# SaxStat_01.net
KiCad netlist of a schematic drawn in EasyEDA Pro
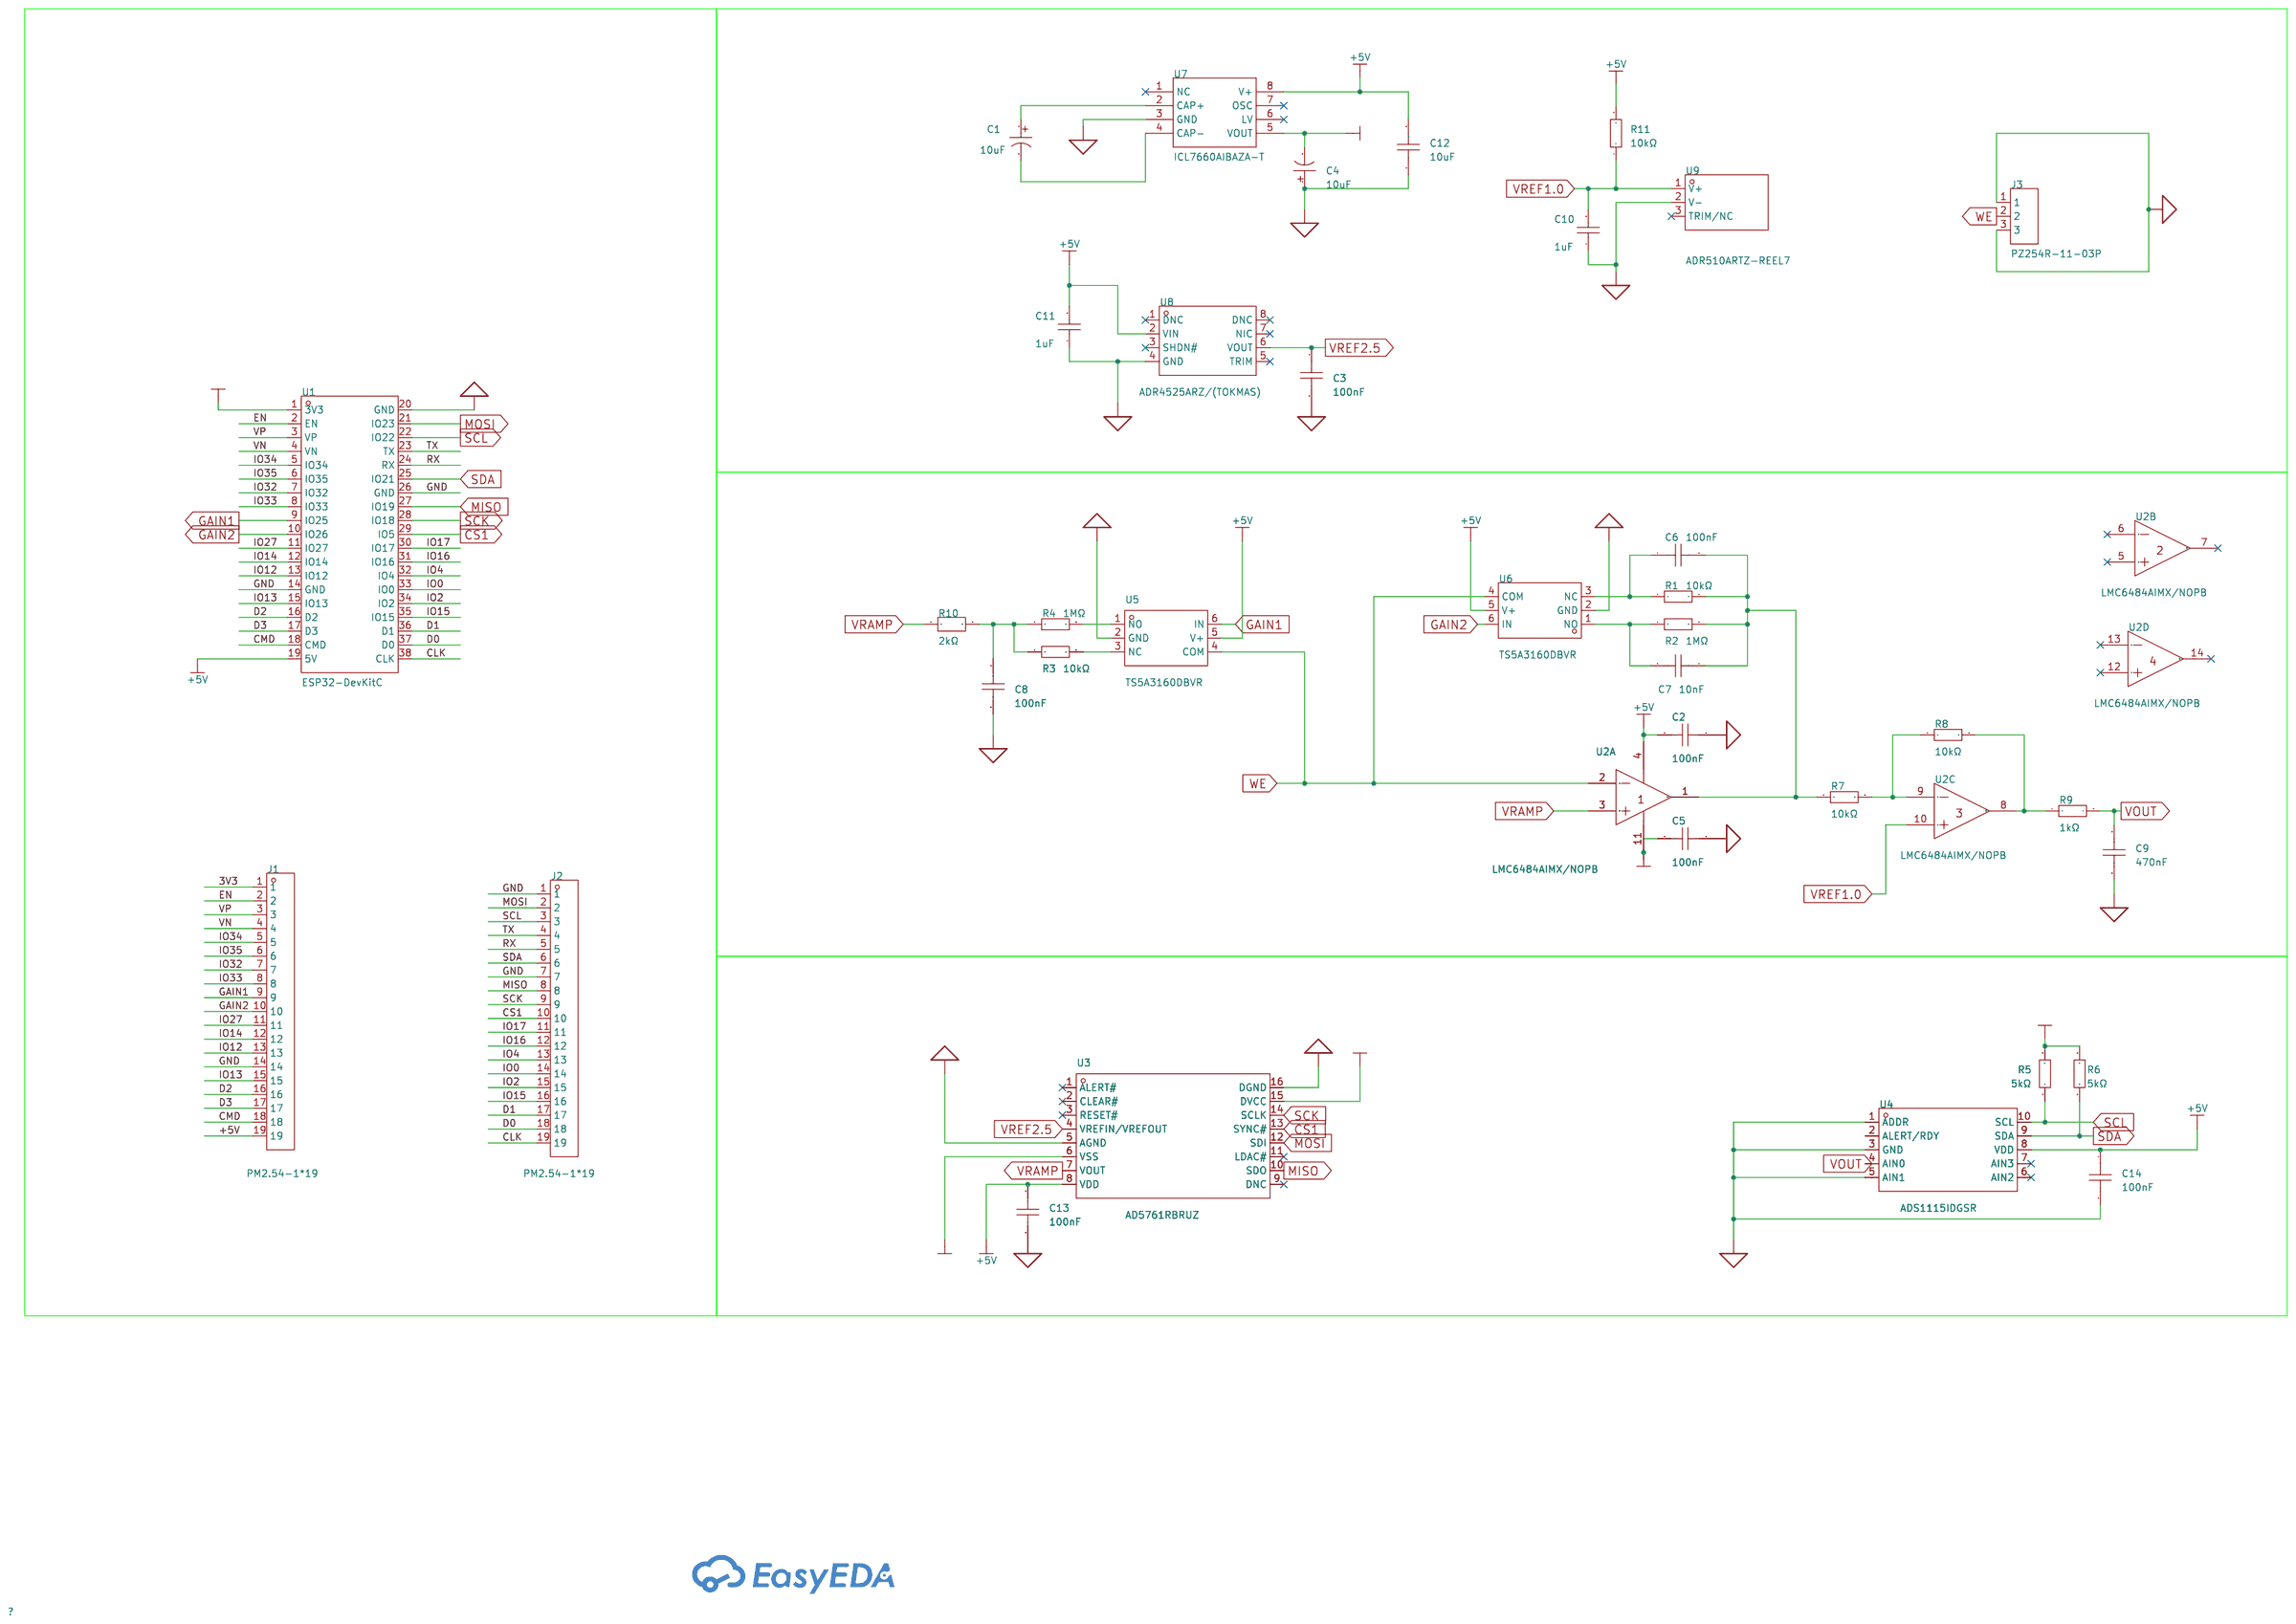
[diagram p0: schematic sheet]

(export (version "E")
  (design (tool "Eeschema 10.0.6"))
  (components
    (comp (ref "C1")
      (value "10uF")
      (footprint "easyedapro:CAP-SMD_BD4.0-L4.3-W4.3-FD")
      (fields (field (name "Manufacturer Part") "RVT1E100M0405") (field (name "Manufacturer") "HONOR(荣誉)"))
      (libsource (lib "easyedapro") (part "RVT1E100M0405"))
    )
    (comp (ref "C2")
      (value "100nF")
      (footprint "easyedapro:C0201")
      (fields
        (field (name "Manufacturer Part") "CL03A104KQ3NNNC")
        (field (name "Manufacturer") "SAMSUNG(三星)")
      )
      (libsource (lib "easyedapro") (part "CL03A104KQ3NNNC"))
    )
    (comp (ref "C3")
      (value "100nF")
      (footprint "easyedapro:C0201")
      (fields
        (field (name "Manufacturer Part") "CL03A104KQ3NNNC")
        (field (name "Manufacturer") "SAMSUNG(三星)")
      )
      (libsource (lib "easyedapro") (part "CL03A104KQ3NNNC"))
    )
    (comp (ref "C4")
      (value "10uF")
      (footprint "easyedapro:CAP-SMD_BD4.0-L4.3-W4.3-FD")
      (fields (field (name "Manufacturer Part") "RVT1E100M0405") (field (name "Manufacturer") "HONOR(荣誉)"))
      (libsource (lib "easyedapro") (part "RVT1E100M0405"))
    )
    (comp (ref "C5")
      (value "100nF")
      (footprint "easyedapro:C0201")
      (fields
        (field (name "Manufacturer Part") "CL03A104KQ3NNNC")
        (field (name "Manufacturer") "SAMSUNG(三星)")
      )
      (libsource (lib "easyedapro") (part "CL03A104KQ3NNNC"))
    )
    (comp (ref "C6")
      (value "100nF")
      (footprint "easyedapro:C0201")
      (fields
        (field (name "Manufacturer Part") "CL03A104KQ3NNNC")
        (field (name "Manufacturer") "SAMSUNG(三星)")
      )
      (libsource (lib "easyedapro") (part "CL03A104KQ3NNNC"))
    )
    (comp (ref "C7")
      (value "10nF")
      (footprint "easyedapro:C0201")
      (fields
        (field (name "Manufacturer Part") "CL03A103KP3NNNC")
        (field (name "Manufacturer") "SAMSUNG(三星)")
      )
      (libsource (lib "easyedapro") (part "CL03A103KP3NNNC"))
    )
    (comp (ref "C8")
      (value "100nF")
      (footprint "easyedapro:C0201")
      (fields
        (field (name "Manufacturer Part") "CL03A104KQ3NNNC")
        (field (name "Manufacturer") "SAMSUNG(三星)")
      )
      (libsource (lib "easyedapro") (part "CL03A104KQ3NNNC"))
    )
    (comp (ref "C9")
      (value "470nF")
      (footprint "easyedapro:C0201")
      (fields
        (field (name "Manufacturer Part") "CL03A474KQ3NNNC")
        (field (name "Manufacturer") "SAMSUNG(三星)")
      )
      (libsource (lib "easyedapro") (part "CL03A474KQ3NNNC"))
    )
    (comp (ref "C10")
      (value "1uF")
      (footprint "easyedapro:C0201")
      (fields
        (field (name "Manufacturer Part") "CL03A105MQ3CSNH")
        (field (name "Manufacturer") "SAMSUNG(三星)")
      )
      (libsource (lib "easyedapro") (part "CL03A105MQ3CSNH"))
    )
    (comp (ref "C11")
      (value "1uF")
      (footprint "easyedapro:C0201")
      (fields
        (field (name "Manufacturer Part") "CL03A105MQ3CSNH")
        (field (name "Manufacturer") "SAMSUNG(三星)")
      )
      (libsource (lib "easyedapro") (part "CL03A105MQ3CSNH"))
    )
    (comp (ref "C12")
      (value "10uF")
      (footprint "easyedapro:C0402")
      (fields
        (field (name "Manufacturer Part") "CL05A106MP5NUNC")
        (field (name "Manufacturer") "SAMSUNG(三星)")
      )
      (libsource (lib "easyedapro") (part "CL05A106MP5NUNC_C315248"))
    )
    (comp (ref "C13")
      (value "100nF")
      (footprint "easyedapro:C0201")
      (fields
        (field (name "Manufacturer Part") "CL03A104KQ3NNNC")
        (field (name "Manufacturer") "SAMSUNG(三星)")
      )
      (libsource (lib "easyedapro") (part "CL03A104KQ3NNNC"))
    )
    (comp (ref "C14")
      (value "100nF")
      (footprint "easyedapro:C0201")
      (fields
        (field (name "Manufacturer Part") "CL03A104KQ3NNNC")
        (field (name "Manufacturer") "SAMSUNG(三星)")
      )
      (libsource (lib "easyedapro") (part "CL03A104KQ3NNNC"))
    )
    (comp (ref "J1")
      (value "PM2.54-1*19")
      (footprint "easyedapro:HDR-TH_19P-P2.54-V-F")
      (description "Holes Structure:1x19P Pitch:2.54mm Number of Rows:Single Row Contact Plating:Gold")
      (fields (field (name "Manufacturer") "ZHOURI(洲日)"))
      (libsource (lib "easyedapro") (part "PM2.54-1*19"))
    )
    (comp (ref "J2")
      (value "PM2.54-1*19")
      (footprint "easyedapro:HDR-TH_19P-P2.54-V-F")
      (description "Holes Structure:1x19P Pitch:2.54mm Number of Rows:Single Row Contact Plating:Gold")
      (fields (field (name "Manufacturer") "ZHOURI(洲日)"))
      (libsource (lib "easyedapro") (part "PM2.54-1*19"))
    )
    (comp (ref "J3")
      (value "PZ254R-11-03P")
      (footprint "easyedapro:HDR-TH_3P-P2.54-H-M-W10.4")
      (fields (field (name "Manufacturer") "XFCN(兴飞)"))
      (libsource (lib "easyedapro") (part "PZ254R-11-03P"))
    )
    (comp (ref "R1")
      (value "10kΩ")
      (footprint "easyedapro:R0603")
      (fields (field (name "Manufacturer Part") "ARG03BTC1002") (field (name "Manufacturer") "Viking(光颉)"))
      (libsource (lib "easyedapro") (part "ARG03BTC1002"))
    )
    (comp (ref "R2")
      (value "1MΩ")
      (footprint "easyedapro:R0603")
      (fields (field (name "Manufacturer Part") "RT0603BRD071ML") (field (name "Manufacturer") "YAGEO(国巨)"))
      (libsource (lib "easyedapro") (part "RT0603BRD071ML"))
    )
    (comp (ref "R3")
      (value "10kΩ")
      (footprint "easyedapro:R0603")
      (fields (field (name "Manufacturer Part") "ARG03BTC1002") (field (name "Manufacturer") "Viking(光颉)"))
      (libsource (lib "easyedapro") (part "ARG03BTC1002"))
    )
    (comp (ref "R4")
      (value "1MΩ")
      (footprint "easyedapro:R0603")
      (fields (field (name "Manufacturer Part") "RT0603BRD071ML") (field (name "Manufacturer") "YAGEO(国巨)"))
      (libsource (lib "easyedapro") (part "RT0603BRD071ML"))
    )
    (comp (ref "R5")
      (value "5kΩ")
      (footprint "easyedapro:R0603")
      (fields (field (name "Manufacturer Part") "RT0603BRE075KL") (field (name "Manufacturer") "YAGEO(国巨)"))
      (libsource (lib "easyedapro") (part "RT0603BRE075KL"))
    )
    (comp (ref "R6")
      (value "5kΩ")
      (footprint "easyedapro:R0603")
      (fields (field (name "Manufacturer Part") "RT0603BRE075KL") (field (name "Manufacturer") "YAGEO(国巨)"))
      (libsource (lib "easyedapro") (part "RT0603BRE075KL"))
    )
    (comp (ref "R7")
      (value "10kΩ")
      (footprint "easyedapro:R0603")
      (fields (field (name "Manufacturer Part") "ARG03BTC1002") (field (name "Manufacturer") "Viking(光颉)"))
      (libsource (lib "easyedapro") (part "ARG03BTC1002"))
    )
    (comp (ref "R8")
      (value "10kΩ")
      (footprint "easyedapro:R0603")
      (fields (field (name "Manufacturer Part") "ARG03BTC1002") (field (name "Manufacturer") "Viking(光颉)"))
      (libsource (lib "easyedapro") (part "ARG03BTC1002"))
    )
    (comp (ref "R9")
      (value "1kΩ")
      (footprint "easyedapro:R0603")
      (fields (field (name "Manufacturer Part") "RT0603BRD071KL") (field (name "Manufacturer") "YAGEO(国巨)"))
      (libsource (lib "easyedapro") (part "RT0603BRD071KL"))
    )
    (comp (ref "R10")
      (value "2kΩ")
      (footprint "easyedapro:R0603")
      (fields (field (name "Manufacturer Part") "RT0603BRD072KL") (field (name "Manufacturer") "YAGEO(国巨)"))
      (libsource (lib "easyedapro") (part "RT0603BRD072KL"))
    )
    (comp (ref "R11")
      (value "10kΩ")
      (footprint "easyedapro:R0603")
      (fields (field (name "Manufacturer Part") "ARG03BTC1002") (field (name "Manufacturer") "Viking(光颉)"))
      (libsource (lib "easyedapro") (part "ARG03BTC1002"))
    )
    (comp (ref "U1")
      (value "ESP32-DevKitC")
      (footprint "easyedapro:BULETM-SMD_ESP32-DEVKITC")
      (fields (field (name "Manufacturer") "ESPRESSIF(乐鑫)"))
      (libsource (lib "easyedapro") (part "ESP32-DEVKITC"))
    )
    (comp (ref "U2")
      (value "LMC6484AIMX/NOPB")
      (footprint "easyedapro:SOIC-14_L8.7-W3.9-P1.27-LS6.0-BL")
      (fields (field (name "Manufacturer") "TI(德州仪器)"))
      (libsource (lib "easyedapro") (part "LMC6484AIMX/NOPB"))
    )
    (comp (ref "U3")
      (value "AD5761RBRUZ")
      (footprint "easyedapro:TSSOP-16_L5.0-W4.4-P0.65-LS6.4-TL")
      (fields (field (name "Manufacturer") "ADI(亚德诺)"))
      (libsource (lib "easyedapro") (part "AD5761RBRUZ"))
    )
    (comp (ref "U4")
      (value "ADS1115IDGSR")
      (footprint "easyedapro:MSOP-10_L3.0-W3.0-P0.50-LS5.0-BL")
      (fields (field (name "Manufacturer") "TI(德州仪器)"))
      (libsource (lib "easyedapro") (part "ADS1115IDGSR"))
    )
    (comp (ref "U5")
      (value "TS5A3160DBVR")
      (footprint "easyedapro:SOT-23-6_L2.9-W1.6-P0.95-LS2.8-BR")
      (fields (field (name "Manufacturer") "TI(德州仪器)"))
      (libsource (lib "easyedapro") (part "TS5A3160DBVR"))
    )
    (comp (ref "U6")
      (value "TS5A3160DBVR")
      (footprint "easyedapro:SOT-23-6_L2.9-W1.6-P0.95-LS2.8-BR")
      (fields (field (name "Manufacturer") "TI(德州仪器)"))
      (libsource (lib "easyedapro") (part "TS5A3160DBVR"))
    )
    (comp (ref "U7")
      (value "ICL7660AIBAZA-T")
      (footprint "easyedapro:SOIC-8_L5.0-W4.0-P1.27-LS6.0-BL")
      (fields (field (name "Manufacturer") "RENESAS(瑞萨)/IDT"))
      (libsource (lib "easyedapro") (part "ICL7660AIBAZA-T"))
    )
    (comp (ref "U8")
      (value "ADR4525ARZ/(TOKMAS)")
      (footprint "easyedapro:SOP-8_L4.9-W3.9-P1.27-LS6.0-BL")
      (fields (field (name "Manufacturer") "Tokmas(托克马斯)"))
      (libsource (lib "easyedapro") (part "ADR4525ARZ/(TOKMAS)"))
    )
    (comp (ref "U9")
      (value "ADR510ARTZ-REEL7")
      (footprint "easyedapro:SOT-23-3_L2.9-W1.3-P1.90-LS2.4-BR")
      (fields (field (name "Manufacturer") "ADI(亚德诺)"))
      (libsource (lib "easyedapro") (part "ADR510ARTZ-REEL7"))
    )
  )
  (nets
    (net (code "1") (name "+5V") (class "Default")
      (node (ref "C11") (pin "2") (pinfunction "2_2") (pintype "input"))
      (node (ref "C12") (pin "2") (pinfunction "2_2") (pintype "unspecified"))
      (node (ref "C13") (pin "1") (pinfunction "1_1") (pintype "unspecified"))
      (node (ref "C14") (pin "1") (pinfunction "1_1") (pintype "unspecified"))
      (node (ref "C2") (pin "1") (pinfunction "1_1") (pintype "unspecified"))
      (node (ref "J1") (pin "19") (pinfunction "19_19") (pintype "unspecified"))
      (node (ref "R11") (pin "2") (pinfunction "2_2") (pintype "unspecified"))
      (node (ref "U1") (pin "19") (pinfunction "5V_19") (pintype "unspecified"))
      (node (ref "U2") (pin "4") (pinfunction "V+_4") (pintype "unspecified"))
      (node (ref "U3") (pin "8") (pinfunction "VDD_8") (pintype "unspecified"))
      (node (ref "U4") (pin "8") (pinfunction "VDD_8") (pintype "unspecified"))
      (node (ref "U5") (pin "5") (pinfunction "V+_5") (pintype "unspecified"))
      (node (ref "U6") (pin "5") (pinfunction "V+_5") (pintype "unspecified"))
      (node (ref "U7") (pin "8") (pinfunction "V+_8") (pintype "unspecified"))
      (node (ref "U8") (pin "2") (pinfunction "VIN_2") (pintype "unspecified"))
    )
    (net (code "2") (name "-5V") (class "Default")
      (node (ref "C4") (pin "2") (pinfunction "2_2") (pintype "input"))
      (node (ref "C5") (pin "1") (pinfunction "1_1") (pintype "unspecified"))
      (node (ref "U2") (pin "11") (pinfunction "V-_11") (pintype "unspecified"))
      (node (ref "U3") (pin "6") (pinfunction "VSS_6") (pintype "unspecified"))
      (node (ref "U7") (pin "5") (pinfunction "VOUT_5") (pintype "unspecified"))
    )
    (net (code "3") (name "/CLK") (class "Default")
      (node (ref "J2") (pin "19") (pinfunction "19_19") (pintype "unspecified"))
      (node (ref "U1") (pin "38") (pinfunction "CLK_38") (pintype "unspecified"))
    )
    (net (code "4") (name "/CMD") (class "Default")
      (node (ref "J1") (pin "18") (pinfunction "18_18") (pintype "unspecified"))
      (node (ref "U1") (pin "18") (pinfunction "CMD_18") (pintype "unspecified"))
    )
    (net (code "5") (name "/D0") (class "Default")
      (node (ref "J2") (pin "18") (pinfunction "18_18") (pintype "unspecified"))
      (node (ref "U1") (pin "37") (pinfunction "D0_37") (pintype "unspecified"))
    )
    (net (code "6") (name "/D1") (class "Default")
      (node (ref "J2") (pin "17") (pinfunction "17_17") (pintype "unspecified"))
      (node (ref "U1") (pin "36") (pinfunction "D1_36") (pintype "unspecified"))
    )
    (net (code "7") (name "/D2") (class "Default")
      (node (ref "J1") (pin "16") (pinfunction "16_16") (pintype "unspecified"))
      (node (ref "U1") (pin "16") (pinfunction "D2_16") (pintype "unspecified"))
    )
    (net (code "8") (name "/D3") (class "Default")
      (node (ref "J1") (pin "17") (pinfunction "17_17") (pintype "unspecified"))
      (node (ref "U1") (pin "17") (pinfunction "D3_17") (pintype "unspecified"))
    )
    (net (code "9") (name "/EN") (class "Default")
      (node (ref "J1") (pin "2") (pinfunction "2_2") (pintype "unspecified"))
      (node (ref "U1") (pin "2") (pinfunction "EN_2") (pintype "unspecified"))
    )
    (net (code "10") (name "/IO0") (class "Default")
      (node (ref "J2") (pin "14") (pinfunction "14_14") (pintype "unspecified"))
      (node (ref "U1") (pin "33") (pinfunction "IO0_33") (pintype "unspecified"))
    )
    (net (code "11") (name "/IO2") (class "Default")
      (node (ref "J2") (pin "15") (pinfunction "15_15") (pintype "unspecified"))
      (node (ref "U1") (pin "34") (pinfunction "IO2_34") (pintype "unspecified"))
    )
    (net (code "12") (name "/IO4") (class "Default")
      (node (ref "J2") (pin "13") (pinfunction "13_13") (pintype "unspecified"))
      (node (ref "U1") (pin "32") (pinfunction "IO4_32") (pintype "unspecified"))
    )
    (net (code "13") (name "/IO12") (class "Default")
      (node (ref "J1") (pin "13") (pinfunction "13_13") (pintype "unspecified"))
      (node (ref "U1") (pin "13") (pinfunction "IO12_13") (pintype "unspecified"))
    )
    (net (code "14") (name "/IO13") (class "Default")
      (node (ref "J1") (pin "15") (pinfunction "15_15") (pintype "unspecified"))
      (node (ref "U1") (pin "15") (pinfunction "IO13_15") (pintype "unspecified"))
    )
    (net (code "15") (name "/IO14") (class "Default")
      (node (ref "J1") (pin "12") (pinfunction "12_12") (pintype "unspecified"))
      (node (ref "U1") (pin "12") (pinfunction "IO14_12") (pintype "unspecified"))
    )
    (net (code "16") (name "/IO15") (class "Default")
      (node (ref "J2") (pin "16") (pinfunction "16_16") (pintype "unspecified"))
      (node (ref "U1") (pin "35") (pinfunction "IO15_35") (pintype "unspecified"))
    )
    (net (code "17") (name "/IO16") (class "Default")
      (node (ref "J2") (pin "12") (pinfunction "12_12") (pintype "unspecified"))
      (node (ref "U1") (pin "31") (pinfunction "IO16_31") (pintype "unspecified"))
    )
    (net (code "18") (name "/IO17") (class "Default")
      (node (ref "J2") (pin "11") (pinfunction "11_11") (pintype "unspecified"))
      (node (ref "U1") (pin "30") (pinfunction "IO17_30") (pintype "unspecified"))
    )
    (net (code "19") (name "/IO27") (class "Default")
      (node (ref "J1") (pin "11") (pinfunction "11_11") (pintype "unspecified"))
      (node (ref "U1") (pin "11") (pinfunction "IO27_11") (pintype "unspecified"))
    )
    (net (code "20") (name "/IO32") (class "Default")
      (node (ref "J1") (pin "7") (pinfunction "7_7") (pintype "unspecified"))
      (node (ref "U1") (pin "7") (pinfunction "IO32_7") (pintype "unspecified"))
    )
    (net (code "21") (name "/IO33") (class "Default")
      (node (ref "J1") (pin "8") (pinfunction "8_8") (pintype "unspecified"))
      (node (ref "U1") (pin "8") (pinfunction "IO33_8") (pintype "unspecified"))
    )
    (net (code "22") (name "/IO34") (class "Default")
      (node (ref "J1") (pin "5") (pinfunction "5_5") (pintype "unspecified"))
      (node (ref "U1") (pin "5") (pinfunction "IO34_5") (pintype "unspecified"))
    )
    (net (code "23") (name "/IO35") (class "Default")
      (node (ref "J1") (pin "6") (pinfunction "6_6") (pintype "unspecified"))
      (node (ref "U1") (pin "6") (pinfunction "IO35_6") (pintype "unspecified"))
    )
    (net (code "24") (name "/RX") (class "Default")
      (node (ref "J2") (pin "5") (pinfunction "5_5") (pintype "unspecified"))
      (node (ref "U1") (pin "24") (pinfunction "RX_24") (pintype "unspecified"))
    )
    (net (code "25") (name "/TX") (class "Default")
      (node (ref "J2") (pin "4") (pinfunction "4_4") (pintype "unspecified"))
      (node (ref "U1") (pin "23") (pinfunction "TX_23") (pintype "unspecified"))
    )
    (net (code "26") (name "/VN") (class "Default")
      (node (ref "J1") (pin "4") (pinfunction "4_4") (pintype "unspecified"))
      (node (ref "U1") (pin "4") (pinfunction "VN_4") (pintype "unspecified"))
    )
    (net (code "27") (name "/VP") (class "Default")
      (node (ref "J1") (pin "3") (pinfunction "3_3") (pintype "unspecified"))
      (node (ref "U1") (pin "3") (pinfunction "VP_3") (pintype "unspecified"))
    )
    (net (code "28") (name "3V3") (class "Default")
      (node (ref "J1") (pin "1") (pinfunction "1_1") (pintype "unspecified"))
      (node (ref "R5") (pin "2") (pinfunction "2_2") (pintype "unspecified"))
      (node (ref "R6") (pin "2") (pinfunction "2_2") (pintype "unspecified"))
      (node (ref "U1") (pin "1") (pinfunction "3V3_1") (pintype "unspecified"))
      (node (ref "U3") (pin "15") (pinfunction "DVCC_15") (pintype "unspecified"))
    )
    (net (code "29") (name "CS1") (class "Default")
      (node (ref "J2") (pin "10") (pinfunction "10_10") (pintype "unspecified"))
      (node (ref "U1") (pin "29") (pinfunction "IO5_29") (pintype "unspecified"))
      (node (ref "U3") (pin "13") (pinfunction "SYNC#_13") (pintype "unspecified"))
    )
    (net (code "30") (name "GAIN1") (class "Default")
      (node (ref "J1") (pin "9") (pinfunction "9_9") (pintype "unspecified"))
      (node (ref "U1") (pin "9") (pinfunction "IO25_9") (pintype "unspecified"))
      (node (ref "U5") (pin "6") (pinfunction "IN_6") (pintype "unspecified"))
    )
    (net (code "31") (name "GAIN2") (class "Default")
      (node (ref "J1") (pin "10") (pinfunction "10_10") (pintype "unspecified"))
      (node (ref "U1") (pin "10") (pinfunction "IO26_10") (pintype "unspecified"))
      (node (ref "U6") (pin "6") (pinfunction "IN_6") (pintype "unspecified"))
    )
    (net (code "32") (name "GND") (class "Default")
      (node (ref "C10") (pin "1") (pinfunction "1_1") (pintype "input"))
      (node (ref "C11") (pin "1") (pinfunction "1_1") (pintype "input"))
      (node (ref "C12") (pin "1") (pinfunction "1_1") (pintype "unspecified"))
      (node (ref "C13") (pin "2") (pinfunction "2_2") (pintype "unspecified"))
      (node (ref "C14") (pin "2") (pinfunction "2_2") (pintype "unspecified"))
      (node (ref "C2") (pin "2") (pinfunction "2_2") (pintype "unspecified"))
      (node (ref "C3") (pin "2") (pinfunction "2_2") (pintype "unspecified"))
      (node (ref "C4") (pin "1") (pinfunction "1_1") (pintype "input"))
      (node (ref "C5") (pin "2") (pinfunction "2_2") (pintype "unspecified"))
      (node (ref "C8") (pin "2") (pinfunction "2_2") (pintype "unspecified"))
      (node (ref "C9") (pin "2") (pinfunction "2_2") (pintype "unspecified"))
      (node (ref "J1") (pin "14") (pinfunction "14_14") (pintype "unspecified"))
      (node (ref "J2") (pin "1") (pinfunction "1_1") (pintype "unspecified"))
      (node (ref "J2") (pin "7") (pinfunction "7_7") (pintype "unspecified"))
      (node (ref "J3") (pin "1") (pinfunction "1_1") (pintype "unspecified"))
      (node (ref "J3") (pin "3") (pinfunction "3_3") (pintype "unspecified"))
      (node (ref "U1") (pin "14") (pinfunction "GND_14") (pintype "unspecified"))
      (node (ref "U1") (pin "20") (pinfunction "GND_20") (pintype "unspecified"))
      (node (ref "U1") (pin "26") (pinfunction "GND_26") (pintype "unspecified"))
      (node (ref "U3") (pin "16") (pinfunction "DGND_16") (pintype "unspecified"))
      (node (ref "U3") (pin "5") (pinfunction "AGND_5") (pintype "unspecified"))
      (node (ref "U4") (pin "1") (pinfunction "ADDR_1") (pintype "unspecified"))
      (node (ref "U4") (pin "3") (pinfunction "GND_3") (pintype "unspecified"))
      (node (ref "U4") (pin "5") (pinfunction "AIN1_5") (pintype "unspecified"))
      (node (ref "U5") (pin "2") (pinfunction "GND_2") (pintype "unspecified"))
      (node (ref "U6") (pin "2") (pinfunction "GND_2") (pintype "unspecified"))
      (node (ref "U7") (pin "3") (pinfunction "GND_3") (pintype "unspecified"))
      (node (ref "U8") (pin "4") (pinfunction "GND_4") (pintype "unspecified"))
      (node (ref "U9") (pin "2") (pinfunction "V-_2") (pintype "unspecified"))
    )
    (net (code "33") (name "MISO") (class "Default")
      (node (ref "J2") (pin "8") (pinfunction "8_8") (pintype "unspecified"))
      (node (ref "U1") (pin "27") (pinfunction "IO19_27") (pintype "unspecified"))
      (node (ref "U3") (pin "10") (pinfunction "SDO_10") (pintype "unspecified"))
    )
    (net (code "34") (name "MOSI") (class "Default")
      (node (ref "J2") (pin "2") (pinfunction "2_2") (pintype "unspecified"))
      (node (ref "U1") (pin "21") (pinfunction "IO23_21") (pintype "unspecified"))
      (node (ref "U3") (pin "12") (pinfunction "SDI_12") (pintype "unspecified"))
    )
    (net (code "35") (name "Net-(C8-Pad1)") (class "Default")
      (node (ref "C8") (pin "1") (pinfunction "1_1") (pintype "unspecified"))
      (node (ref "R10") (pin "2") (pinfunction "2_2") (pintype "unspecified"))
      (node (ref "R3") (pin "1") (pinfunction "1_1") (pintype "unspecified"))
      (node (ref "R4") (pin "1") (pinfunction "1_1") (pintype "unspecified"))
    )
    (net (code "36") (name "Net-(U2A-OUT1)") (class "Default")
      (node (ref "C6") (pin "2") (pinfunction "2_2") (pintype "unspecified"))
      (node (ref "C7") (pin "1") (pinfunction "1_1") (pintype "unspecified"))
      (node (ref "R1") (pin "2") (pinfunction "2_2") (pintype "unspecified"))
      (node (ref "R2") (pin "2") (pinfunction "2_2") (pintype "unspecified"))
      (node (ref "R7") (pin "1") (pinfunction "1_1") (pintype "unspecified"))
      (node (ref "U2") (pin "1") (pinfunction "OUT1_1") (pintype "output"))
    )
    (net (code "37") (name "Net-(U2C-IN3-)") (class "Default")
      (node (ref "R7") (pin "2") (pinfunction "2_2") (pintype "unspecified"))
      (node (ref "R8") (pin "1") (pinfunction "1_1") (pintype "unspecified"))
      (node (ref "U2") (pin "9") (pinfunction "IN3-_9") (pintype "unspecified"))
    )
    (net (code "38") (name "Net-(U2C-OUT3)") (class "Default")
      (node (ref "R8") (pin "2") (pinfunction "2_2") (pintype "unspecified"))
      (node (ref "R9") (pin "1") (pinfunction "1_1") (pintype "input"))
      (node (ref "U2") (pin "8") (pinfunction "OUT3_8") (pintype "output"))
    )
    (net (code "39") (name "Net-(U5-NC)") (class "Default")
      (node (ref "R3") (pin "2") (pinfunction "2_2") (pintype "unspecified"))
      (node (ref "U5") (pin "3") (pinfunction "NC_3") (pintype "unspecified"))
    )
    (net (code "40") (name "Net-(U5-NO)") (class "Default")
      (node (ref "R4") (pin "2") (pinfunction "2_2") (pintype "unspecified"))
      (node (ref "U5") (pin "1") (pinfunction "NO_1") (pintype "unspecified"))
    )
    (net (code "41") (name "Net-(U6-NC)") (class "Default")
      (node (ref "C6") (pin "1") (pinfunction "1_1") (pintype "unspecified"))
      (node (ref "R1") (pin "1") (pinfunction "1_1") (pintype "unspecified"))
      (node (ref "U6") (pin "3") (pinfunction "NC_3") (pintype "unspecified"))
    )
    (net (code "42") (name "Net-(U6-NO)") (class "Default")
      (node (ref "C7") (pin "2") (pinfunction "2_2") (pintype "unspecified"))
      (node (ref "R2") (pin "1") (pinfunction "1_1") (pintype "unspecified"))
      (node (ref "U6") (pin "1") (pinfunction "NO_1") (pintype "unspecified"))
    )
    (net (code "43") (name "Net-(U7-CAP+)") (class "Default")
      (node (ref "C1") (pin "1") (pinfunction "1_1") (pintype "input"))
      (node (ref "U7") (pin "2") (pinfunction "CAP+_2") (pintype "unspecified"))
    )
    (net (code "44") (name "Net-(U7-CAP-)") (class "Default")
      (node (ref "C1") (pin "2") (pinfunction "2_2") (pintype "input"))
      (node (ref "U7") (pin "4") (pinfunction "CAP-_4") (pintype "unspecified"))
    )
    (net (code "45") (name "SCK") (class "Default")
      (node (ref "J2") (pin "9") (pinfunction "9_9") (pintype "unspecified"))
      (node (ref "U1") (pin "28") (pinfunction "IO18_28") (pintype "unspecified"))
      (node (ref "U3") (pin "14") (pinfunction "SCLK_14") (pintype "unspecified"))
    )
    (net (code "46") (name "SCL") (class "Default")
      (node (ref "J2") (pin "3") (pinfunction "3_3") (pintype "unspecified"))
      (node (ref "R5") (pin "1") (pinfunction "1_1") (pintype "unspecified"))
      (node (ref "U1") (pin "22") (pinfunction "IO22_22") (pintype "unspecified"))
      (node (ref "U4") (pin "10") (pinfunction "SCL_10") (pintype "unspecified"))
    )
    (net (code "47") (name "SDA") (class "Default")
      (node (ref "J2") (pin "6") (pinfunction "6_6") (pintype "unspecified"))
      (node (ref "R6") (pin "1") (pinfunction "1_1") (pintype "unspecified"))
      (node (ref "U1") (pin "25") (pinfunction "IO21_25") (pintype "unspecified"))
      (node (ref "U4") (pin "9") (pinfunction "SDA_9") (pintype "unspecified"))
    )
    (net (code "48") (name "VOUT") (class "Default")
      (node (ref "C9") (pin "1") (pinfunction "1_1") (pintype "unspecified"))
      (node (ref "R9") (pin "2") (pinfunction "2_2") (pintype "input"))
      (node (ref "U4") (pin "4") (pinfunction "AIN0_4") (pintype "unspecified"))
    )
    (net (code "49") (name "VRAMP") (class "Default")
      (node (ref "R10") (pin "1") (pinfunction "1_1") (pintype "unspecified"))
      (node (ref "U2") (pin "3") (pinfunction "IN1+_3") (pintype "unspecified"))
      (node (ref "U3") (pin "7") (pinfunction "VOUT_7") (pintype "unspecified"))
    )
    (net (code "50") (name "VREF1.0") (class "Default")
      (node (ref "C10") (pin "2") (pinfunction "2_2") (pintype "input"))
      (node (ref "R11") (pin "1") (pinfunction "1_1") (pintype "unspecified"))
      (node (ref "U2") (pin "10") (pinfunction "IN3+_10") (pintype "unspecified"))
      (node (ref "U9") (pin "1") (pinfunction "V+_1") (pintype "unspecified"))
    )
    (net (code "51") (name "VREF2.5") (class "Default")
      (node (ref "C3") (pin "1") (pinfunction "1_1") (pintype "unspecified"))
      (node (ref "U3") (pin "4") (pinfunction "VREFIN/VREFOUT_4") (pintype "unspecified"))
      (node (ref "U8") (pin "6") (pinfunction "VOUT_6") (pintype "unspecified"))
    )
    (net (code "52") (name "WE") (class "Default")
      (node (ref "J3") (pin "2") (pinfunction "2_2") (pintype "unspecified"))
      (node (ref "U2") (pin "2") (pinfunction "IN1-_2") (pintype "unspecified"))
      (node (ref "U5") (pin "4") (pinfunction "COM_4") (pintype "unspecified"))
      (node (ref "U6") (pin "4") (pinfunction "COM_4") (pintype "unspecified"))
    )
    (net (code "53") (name "unconnected-(U2B-IN2+-Pad5)") (class "Default")
      (node (ref "U2") (pin "5") (pinfunction "IN2+_5") (pintype "unspecified+no_connect"))
    )
    (net (code "54") (name "unconnected-(U2B-IN2--Pad6)") (class "Default")
      (node (ref "U2") (pin "6") (pinfunction "IN2-_6") (pintype "unspecified+no_connect"))
    )
    (net (code "55") (name "unconnected-(U2B-OUT2-Pad7)") (class "Default")
      (node (ref "U2") (pin "7") (pinfunction "OUT2_7") (pintype "output+no_connect"))
    )
    (net (code "56") (name "unconnected-(U2D-IN4+-Pad12)") (class "Default")
      (node (ref "U2") (pin "12") (pinfunction "IN4+_12") (pintype "unspecified+no_connect"))
    )
    (net (code "57") (name "unconnected-(U2D-IN4--Pad13)") (class "Default")
      (node (ref "U2") (pin "13") (pinfunction "IN4-_13") (pintype "unspecified+no_connect"))
    )
    (net (code "58") (name "unconnected-(U2D-OUT4-Pad14)") (class "Default")
      (node (ref "U2") (pin "14") (pinfunction "OUT4_14") (pintype "output+no_connect"))
    )
    (net (code "59") (name "unconnected-(U3-ALERT#-Pad1)") (class "Default")
      (node (ref "U3") (pin "1") (pinfunction "ALERT#_1") (pintype "unspecified+no_connect"))
    )
    (net (code "60") (name "unconnected-(U3-CLEAR#-Pad2)") (class "Default")
      (node (ref "U3") (pin "2") (pinfunction "CLEAR#_2") (pintype "unspecified+no_connect"))
    )
    (net (code "61") (name "unconnected-(U3-DNC-Pad9)") (class "Default")
      (node (ref "U3") (pin "9") (pinfunction "DNC_9") (pintype "unspecified+no_connect"))
    )
    (net (code "62") (name "unconnected-(U3-LDAC#-Pad11)") (class "Default")
      (node (ref "U3") (pin "11") (pinfunction "LDAC#_11") (pintype "unspecified+no_connect"))
    )
    (net (code "63") (name "unconnected-(U3-RESET#-Pad3)") (class "Default")
      (node (ref "U3") (pin "3") (pinfunction "RESET#_3") (pintype "unspecified+no_connect"))
    )
    (net (code "64") (name "unconnected-(U4-AIN2-Pad6)") (class "Default")
      (node (ref "U4") (pin "6") (pinfunction "AIN2_6") (pintype "unspecified+no_connect"))
    )
    (net (code "65") (name "unconnected-(U4-AIN3-Pad7)") (class "Default")
      (node (ref "U4") (pin "7") (pinfunction "AIN3_7") (pintype "unspecified+no_connect"))
    )
    (net (code "66") (name "unconnected-(U4-ALERT{slash}RDY-Pad2)") (class "Default")
      (node (ref "U4") (pin "2") (pinfunction "ALERT/RDY_2") (pintype "unspecified"))
    )
    (net (code "67") (name "unconnected-(U7-LV-Pad6)") (class "Default")
      (node (ref "U7") (pin "6") (pinfunction "LV_6") (pintype "unspecified+no_connect"))
    )
    (net (code "68") (name "unconnected-(U7-NC-Pad1)") (class "Default")
      (node (ref "U7") (pin "1") (pinfunction "NC_1") (pintype "unspecified+no_connect"))
    )
    (net (code "69") (name "unconnected-(U7-OSC-Pad7)") (class "Default")
      (node (ref "U7") (pin "7") (pinfunction "OSC_7") (pintype "unspecified+no_connect"))
    )
    (net (code "70") (name "unconnected-(U8-DNC-Pad1)") (class "Default")
      (node (ref "U8") (pin "1") (pinfunction "DNC_1") (pintype "unspecified+no_connect"))
    )
    (net (code "71") (name "unconnected-(U8-DNC-Pad8)") (class "Default")
      (node (ref "U8") (pin "8") (pinfunction "DNC_8") (pintype "unspecified+no_connect"))
    )
    (net (code "72") (name "unconnected-(U8-NIC-Pad7)") (class "Default")
      (node (ref "U8") (pin "7") (pinfunction "NIC_7") (pintype "unspecified+no_connect"))
    )
    (net (code "73") (name "unconnected-(U8-SHDN#-Pad3)") (class "Default")
      (node (ref "U8") (pin "3") (pinfunction "SHDN#_3") (pintype "unspecified+no_connect"))
    )
    (net (code "74") (name "unconnected-(U8-TRIM-Pad5)") (class "Default")
      (node (ref "U8") (pin "5") (pinfunction "TRIM_5") (pintype "unspecified+no_connect"))
    )
    (net (code "75") (name "unconnected-(U9-TRIM{slash}NC-Pad3)") (class "Default")
      (node (ref "U9") (pin "3") (pinfunction "TRIM/NC_3") (pintype "unspecified+no_connect"))
    )
  )
)
